# spdif_A.net
KiCad netlist of a schematic drawn in EAGLE
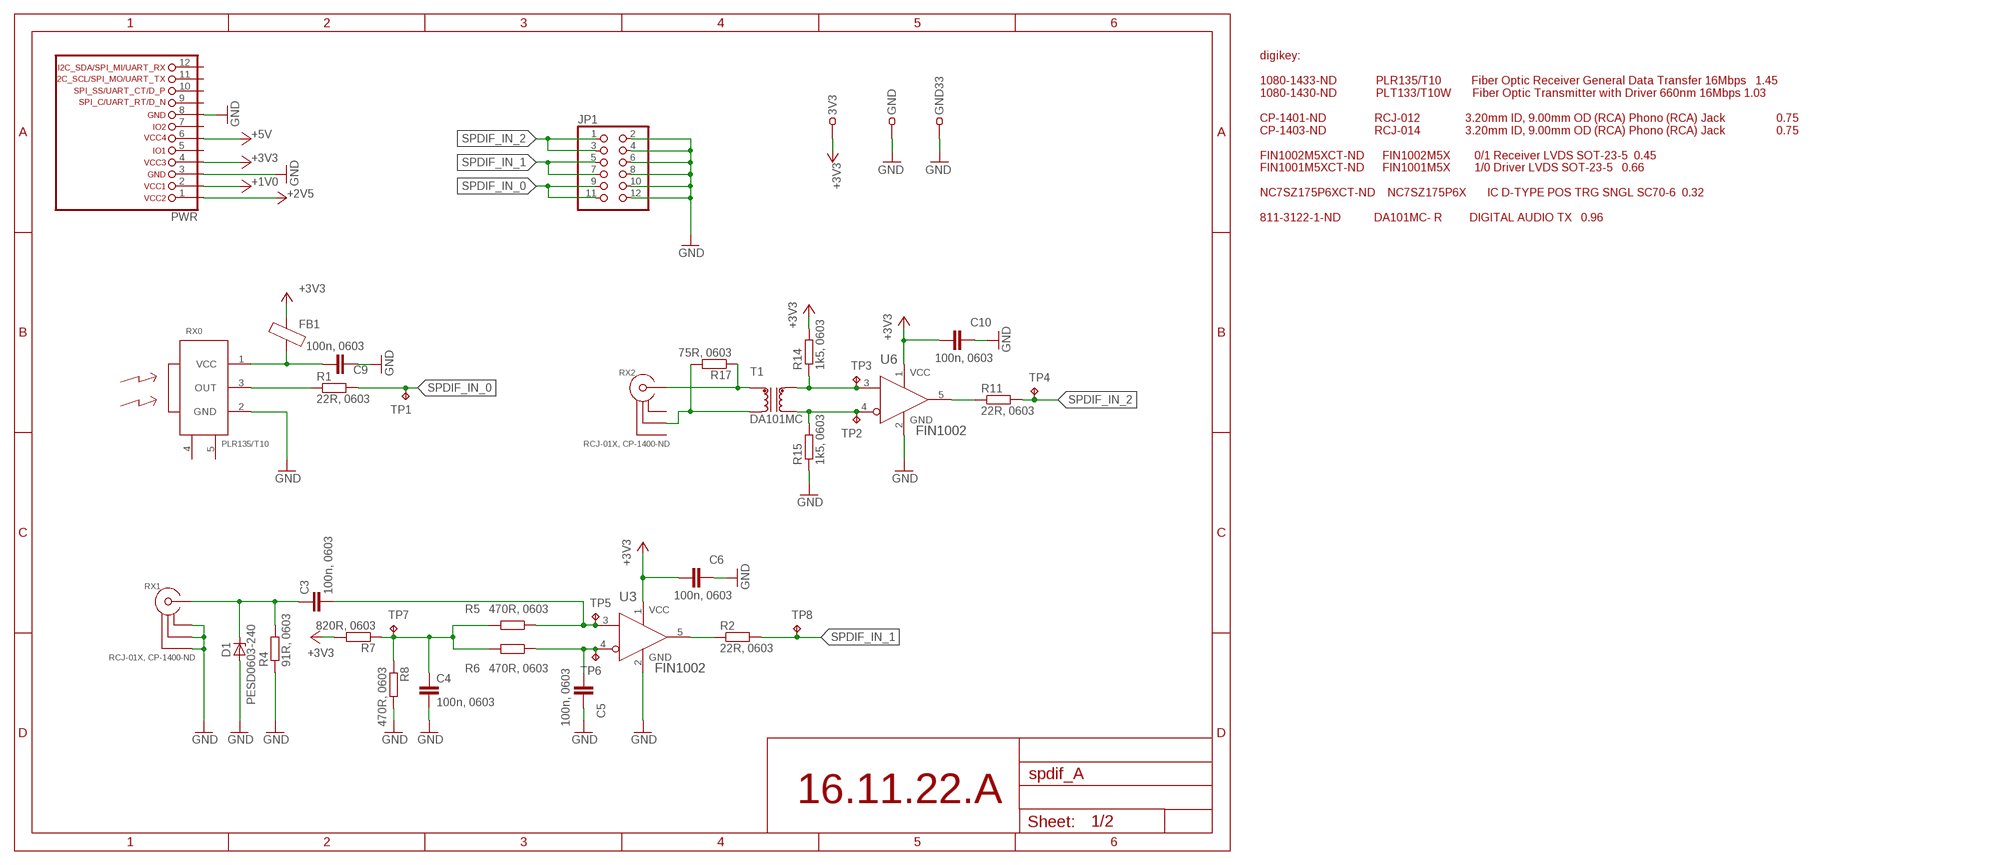
[diagram p0: schematic, sheet 1]
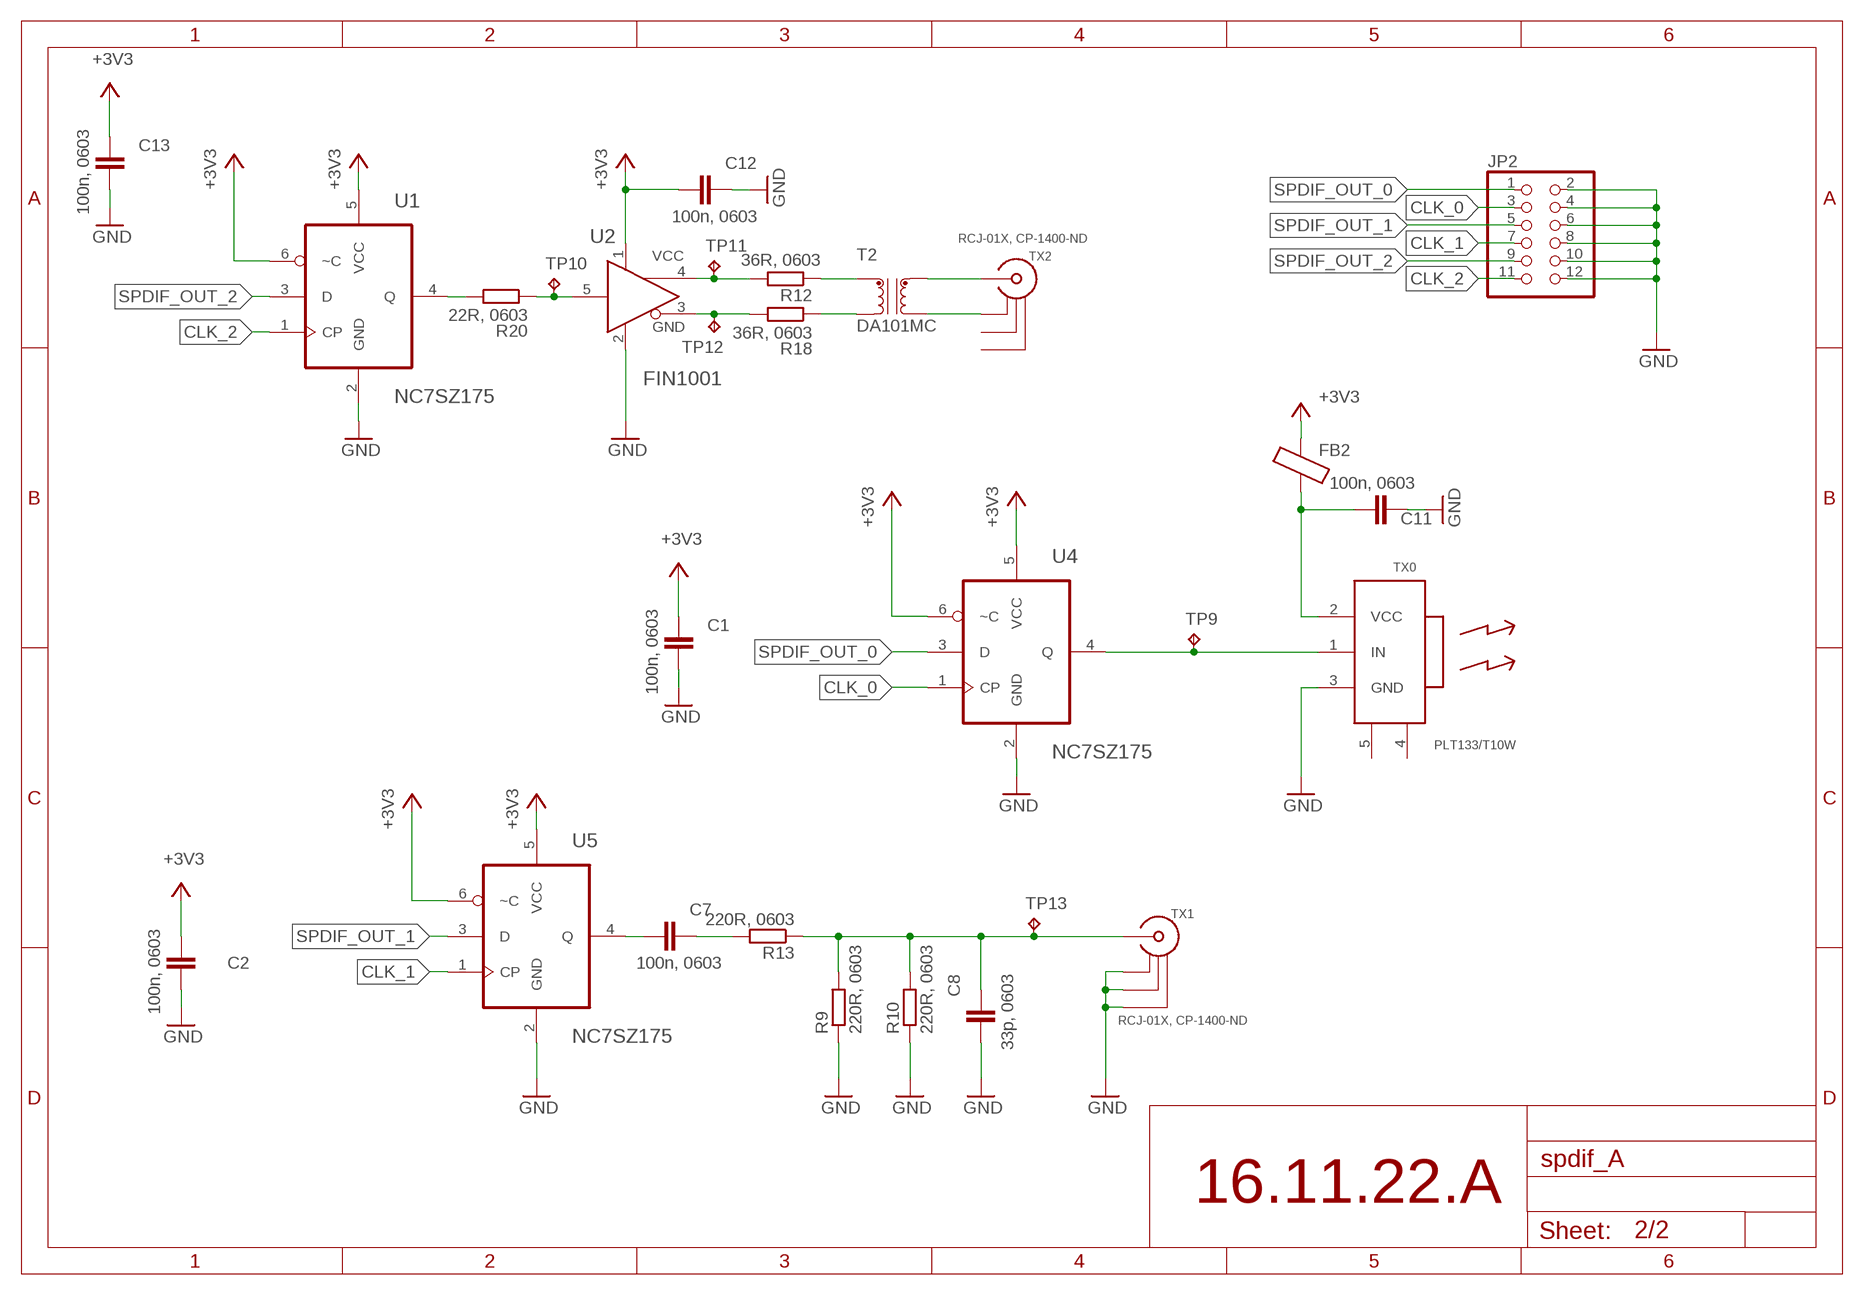
[diagram p1: schematic, sheet 2]

(export (version "E")
  (design (tool "Eeschema 10.0.6"))
  (components
    (comp (ref "3V3")
      (value "TEST-22-MULTICOMP")
      (footprint "eagle-import:TEST_1MM")
      (libsource (lib "eagle-import") (part "TEST-22-MULTICOMP"))
    )
    (comp (ref "C3")
      (value "100n, 0603")
      (footprint "eagle-import:C0603")
      (libsource (lib "eagle-import") (part "C-EUC0603"))
    )
    (comp (ref "C4")
      (value "100n, 0603")
      (footprint "eagle-import:C0603")
      (libsource (lib "eagle-import") (part "C-EUC0603"))
    )
    (comp (ref "C5")
      (value "100n, 0603")
      (footprint "eagle-import:C0603")
      (libsource (lib "eagle-import") (part "C-EUC0603"))
    )
    (comp (ref "C6")
      (value "100n, 0603")
      (footprint "eagle-import:C0603")
      (libsource (lib "eagle-import") (part "C-EUC0603"))
    )
    (comp (ref "C9")
      (value "100n, 0603")
      (footprint "eagle-import:C0603")
      (libsource (lib "eagle-import") (part "C-EUC0603"))
    )
    (comp (ref "C10")
      (value "100n, 0603")
      (footprint "eagle-import:C0603")
      (libsource (lib "eagle-import") (part "C-EUC0603"))
    )
    (comp (ref "D1")
      (value "PESD0603-240")
      (footprint "eagle-import:L0603")
      (libsource (lib "eagle-import") (part "ZDPESD0603-240"))
    )
    (comp (ref "FB1")
      (value "FB_0603")
      (footprint "eagle-import:L0603")
      (libsource (lib "eagle-import") (part "FB_0603"))
    )
    (comp (ref "GND")
      (value "TEST-22-MULTICOMP")
      (footprint "eagle-import:TEST_1MM")
      (libsource (lib "eagle-import") (part "TEST-22-MULTICOMP"))
    )
    (comp (ref "GND33")
      (value "TEST-22-MULTICOMP")
      (footprint "eagle-import:TEST_1MM")
      (libsource (lib "eagle-import") (part "TEST-22-MULTICOMP"))
    )
    (comp (ref "JP1")
      (value "PINHD-2X6/90")
      (footprint "eagle-import:2X06_90")
      (libsource (lib "eagle-import") (part "PINHD-2X6/90"))
    )
    (comp (ref "PWR")
      (value "LIWE_12_PIN_PWR7X7_COMPAT")
      (footprint "eagle-import:LIWE_12_PIN_7X7_COMPAT")
      (libsource (lib "eagle-import") (part "LIWE_12_PIN_PWR7X7_COMPAT"))
    )
    (comp (ref "R1")
      (value "22R, 0603")
      (footprint "eagle-import:R0603")
      (libsource (lib "eagle-import") (part "R-EU_R0603"))
    )
    (comp (ref "R2")
      (value "22R, 0603")
      (footprint "eagle-import:R0603")
      (libsource (lib "eagle-import") (part "R-EU_R0603"))
    )
    (comp (ref "R4")
      (value "91R, 0603")
      (footprint "eagle-import:R0603")
      (libsource (lib "eagle-import") (part "R-EU_R0603"))
    )
    (comp (ref "R5")
      (value "470R, 0603")
      (footprint "eagle-import:R0603")
      (libsource (lib "eagle-import") (part "R-EU_R0603"))
    )
    (comp (ref "R6")
      (value "470R, 0603")
      (footprint "eagle-import:R0603")
      (libsource (lib "eagle-import") (part "R-EU_R0603"))
    )
    (comp (ref "R7")
      (value "820R, 0603")
      (footprint "eagle-import:R0603")
      (libsource (lib "eagle-import") (part "R-EU_R0603"))
    )
    (comp (ref "R8")
      (value "470R, 0603")
      (footprint "eagle-import:R0603")
      (libsource (lib "eagle-import") (part "R-EU_R0603"))
    )
    (comp (ref "R11")
      (value "22R, 0603")
      (footprint "eagle-import:R0603")
      (libsource (lib "eagle-import") (part "R-EU_R0603"))
    )
    (comp (ref "R14")
      (value "1k5, 0603")
      (footprint "eagle-import:R0603")
      (libsource (lib "eagle-import") (part "R-EU_R0603"))
    )
    (comp (ref "R15")
      (value "1k5, 0603")
      (footprint "eagle-import:R0603")
      (libsource (lib "eagle-import") (part "R-EU_R0603"))
    )
    (comp (ref "R17")
      (value "75R, 0603")
      (footprint "eagle-import:R0603")
      (libsource (lib "eagle-import") (part "R-EU_R0603"))
    )
    (comp (ref "RX0")
      (value "PLR135/T10")
      (footprint "eagle-import:PLR135_T10")
      (libsource (lib "eagle-import") (part "PLR135_T10"))
    )
    (comp (ref "RX1")
      (value "RCJ-01X, CP-1400-ND")
      (footprint "eagle-import:RCJ-01X")
      (libsource (lib "eagle-import") (part "RCJ-01X"))
    )
    (comp (ref "RX2")
      (value "RCJ-01X, CP-1400-ND")
      (footprint "eagle-import:RCJ-01X")
      (libsource (lib "eagle-import") (part "RCJ-01X"))
    )
    (comp (ref "T1")
      (value "DA101MC")
      (footprint "eagle-import:DA101MC")
      (libsource (lib "eagle-import") (part "DA101MC"))
    )
    (comp (ref "TP1")
      (value "TPB1,27")
      (footprint "eagle-import:B1,27")
      (libsource (lib "eagle-import") (part "TPB1,27"))
    )
    (comp (ref "TP2")
      (value "TPB1,27")
      (footprint "eagle-import:B1,27")
      (libsource (lib "eagle-import") (part "TPB1,27"))
    )
    (comp (ref "TP3")
      (value "TPB1,27")
      (footprint "eagle-import:B1,27")
      (libsource (lib "eagle-import") (part "TPB1,27"))
    )
    (comp (ref "TP4")
      (value "TPB1,27")
      (footprint "eagle-import:B1,27")
      (libsource (lib "eagle-import") (part "TPB1,27"))
    )
    (comp (ref "TP5")
      (value "TPB1,27")
      (footprint "eagle-import:B1,27")
      (libsource (lib "eagle-import") (part "TPB1,27"))
    )
    (comp (ref "TP6")
      (value "TPB1,27")
      (footprint "eagle-import:B1,27")
      (libsource (lib "eagle-import") (part "TPB1,27"))
    )
    (comp (ref "TP7")
      (value "TPB1,27")
      (footprint "eagle-import:B1,27")
      (libsource (lib "eagle-import") (part "TPB1,27"))
    )
    (comp (ref "TP8")
      (value "TPB1,27")
      (footprint "eagle-import:B1,27")
      (libsource (lib "eagle-import") (part "TPB1,27"))
    )
    (comp (ref "U3")
      (value "FIN1002")
      (footprint "eagle-import:SOT95P280X140-5N")
      (libsource (lib "eagle-import") (part "FIN1002"))
    )
    (comp (ref "U6")
      (value "FIN1002")
      (footprint "eagle-import:SOT95P280X140-5N")
      (libsource (lib "eagle-import") (part "FIN1002"))
    )
    (comp (ref "C1")
      (value "100n, 0603")
      (footprint "eagle-import:C0603")
      (libsource (lib "eagle-import") (part "C-EUC0603"))
    )
    (comp (ref "C2")
      (value "100n, 0603")
      (footprint "eagle-import:C0603")
      (libsource (lib "eagle-import") (part "C-EUC0603"))
    )
    (comp (ref "C7")
      (value "100n, 0603")
      (footprint "eagle-import:C0603")
      (libsource (lib "eagle-import") (part "C-EUC0603"))
    )
    (comp (ref "C8")
      (value "33p, 0603")
      (footprint "eagle-import:C0603")
      (libsource (lib "eagle-import") (part "C-EUC0603"))
    )
    (comp (ref "C11")
      (value "100n, 0603")
      (footprint "eagle-import:C0603")
      (libsource (lib "eagle-import") (part "C-EUC0603"))
    )
    (comp (ref "C12")
      (value "100n, 0603")
      (footprint "eagle-import:C0603")
      (libsource (lib "eagle-import") (part "C-EUC0603"))
    )
    (comp (ref "C13")
      (value "100n, 0603")
      (footprint "eagle-import:C0603")
      (libsource (lib "eagle-import") (part "C-EUC0603"))
    )
    (comp (ref "FB2")
      (value "FB_0603")
      (footprint "eagle-import:L0603")
      (libsource (lib "eagle-import") (part "FB_0603"))
    )
    (comp (ref "JP2")
      (value "PINHD-2X6/90")
      (footprint "eagle-import:2X06_90")
      (libsource (lib "eagle-import") (part "PINHD-2X6/90"))
    )
    (comp (ref "R9")
      (value "220R, 0603")
      (footprint "eagle-import:R0603")
      (libsource (lib "eagle-import") (part "R-EU_R0603"))
    )
    (comp (ref "R10")
      (value "220R, 0603")
      (footprint "eagle-import:R0603")
      (libsource (lib "eagle-import") (part "R-EU_R0603"))
    )
    (comp (ref "R12")
      (value "36R, 0603")
      (footprint "eagle-import:R0603")
      (libsource (lib "eagle-import") (part "R-EU_R0603"))
    )
    (comp (ref "R13")
      (value "220R, 0603")
      (footprint "eagle-import:R0603")
      (libsource (lib "eagle-import") (part "R-EU_R0603"))
    )
    (comp (ref "R18")
      (value "36R, 0603")
      (footprint "eagle-import:R0603")
      (libsource (lib "eagle-import") (part "R-EU_R0603"))
    )
    (comp (ref "R20")
      (value "22R, 0603")
      (footprint "eagle-import:R0603")
      (libsource (lib "eagle-import") (part "R-EU_R0603"))
    )
    (comp (ref "T2")
      (value "DA101MC")
      (footprint "eagle-import:DA101MC")
      (libsource (lib "eagle-import") (part "DA101MC"))
    )
    (comp (ref "TP9")
      (value "TPB1,27")
      (footprint "eagle-import:B1,27")
      (libsource (lib "eagle-import") (part "TPB1,27"))
    )
    (comp (ref "TP10")
      (value "TPB1,27")
      (footprint "eagle-import:B1,27")
      (libsource (lib "eagle-import") (part "TPB1,27"))
    )
    (comp (ref "TP11")
      (value "TPB1,27")
      (footprint "eagle-import:B1,27")
      (libsource (lib "eagle-import") (part "TPB1,27"))
    )
    (comp (ref "TP12")
      (value "TPB1,27")
      (footprint "eagle-import:B1,27")
      (libsource (lib "eagle-import") (part "TPB1,27"))
    )
    (comp (ref "TP13")
      (value "TPB1,27")
      (footprint "eagle-import:B1,27")
      (libsource (lib "eagle-import") (part "TPB1,27"))
    )
    (comp (ref "TX0")
      (value "PLT133/T10W")
      (footprint "eagle-import:PLT133_T10W")
      (libsource (lib "eagle-import") (part "PLT133_T10W"))
    )
    (comp (ref "TX1")
      (value "RCJ-01X, CP-1400-ND")
      (footprint "eagle-import:RCJ-01X")
      (libsource (lib "eagle-import") (part "RCJ-01X"))
    )
    (comp (ref "TX2")
      (value "RCJ-01X, CP-1400-ND")
      (footprint "eagle-import:RCJ-01X")
      (libsource (lib "eagle-import") (part "RCJ-01X"))
    )
    (comp (ref "U1")
      (value "NC7SZ175")
      (footprint "eagle-import:SOT65P210X110-6N")
      (libsource (lib "eagle-import") (part "NC7SZ175"))
    )
    (comp (ref "U2")
      (value "FIN1001")
      (footprint "eagle-import:SOT95P280X140-5N")
      (libsource (lib "eagle-import") (part "FIN1001"))
    )
    (comp (ref "U4")
      (value "NC7SZ175")
      (footprint "eagle-import:SOT65P210X110-6N")
      (libsource (lib "eagle-import") (part "NC7SZ175"))
    )
    (comp (ref "U5")
      (value "NC7SZ175")
      (footprint "eagle-import:SOT65P210X110-6N")
      (libsource (lib "eagle-import") (part "NC7SZ175"))
    )
  )
  (nets
    (net (code "1") (name "+1V0") (class "Default")
      (node (ref "PWR") (pin "2") (pinfunction "2_2") (pintype "passive"))
    )
    (net (code "2") (name "+2V5") (class "Default")
      (node (ref "PWR") (pin "1") (pinfunction "1_1") (pintype "passive"))
    )
    (net (code "3") (name "+3V3") (class "Default")
      (node (ref "3V3") (pin "1") (pinfunction "1_1") (pintype "passive"))
      (node (ref "C1") (pin "2") (pinfunction "2_2") (pintype "passive"))
      (node (ref "C10") (pin "2") (pinfunction "2_2") (pintype "passive"))
      (node (ref "C12") (pin "2") (pinfunction "2_2") (pintype "passive"))
      (node (ref "C13") (pin "2") (pinfunction "2_2") (pintype "passive"))
      (node (ref "C2") (pin "2") (pinfunction "2_2") (pintype "passive"))
      (node (ref "C6") (pin "2") (pinfunction "2_2") (pintype "passive"))
      (node (ref "FB1") (pin "2") (pinfunction "P$2_2") (pintype "bidirectional"))
      (node (ref "FB2") (pin "2") (pinfunction "P$2_2") (pintype "bidirectional"))
      (node (ref "PWR") (pin "4") (pinfunction "4_4") (pintype "passive"))
      (node (ref "R14") (pin "2") (pinfunction "2_2") (pintype "passive"))
      (node (ref "R7") (pin "2") (pinfunction "2_2") (pintype "passive"))
      (node (ref "U1") (pin "5") (pinfunction "VCC_5") (pintype "power_in"))
      (node (ref "U1") (pin "6") (pinfunction "~{C}_6") (pintype "input"))
      (node (ref "U2") (pin "1") (pinfunction "VCC_1") (pintype "power_in"))
      (node (ref "U3") (pin "1") (pinfunction "VCC_1") (pintype "power_in"))
      (node (ref "U4") (pin "5") (pinfunction "VCC_5") (pintype "power_in"))
      (node (ref "U4") (pin "6") (pinfunction "~{C}_6") (pintype "input"))
      (node (ref "U5") (pin "5") (pinfunction "VCC_5") (pintype "power_in"))
      (node (ref "U5") (pin "6") (pinfunction "~{C}_6") (pintype "input"))
      (node (ref "U6") (pin "1") (pinfunction "VCC_1") (pintype "power_in"))
    )
    (net (code "4") (name "+5V") (class "Default")
      (node (ref "PWR") (pin "6") (pinfunction "6_6") (pintype "passive"))
    )
    (net (code "5") (name "CLK_0") (class "Default")
      (node (ref "JP2") (pin "3") (pinfunction "3_3") (pintype "passive"))
      (node (ref "U4") (pin "1") (pinfunction "CP_1") (pintype "input"))
    )
    (net (code "6") (name "CLK_1") (class "Default")
      (node (ref "JP2") (pin "7") (pinfunction "7_7") (pintype "passive"))
      (node (ref "U5") (pin "1") (pinfunction "CP_1") (pintype "input"))
    )
    (net (code "7") (name "CLK_2") (class "Default")
      (node (ref "JP2") (pin "11") (pinfunction "11_11") (pintype "passive"))
      (node (ref "U1") (pin "1") (pinfunction "CP_1") (pintype "input"))
    )
    (net (code "8") (name "GND") (class "Default")
      (node (ref "C1") (pin "1") (pinfunction "1_1") (pintype "passive"))
      (node (ref "C10") (pin "1") (pinfunction "1_1") (pintype "passive"))
      (node (ref "C11") (pin "1") (pinfunction "1_1") (pintype "passive"))
      (node (ref "C12") (pin "1") (pinfunction "1_1") (pintype "passive"))
      (node (ref "C13") (pin "1") (pinfunction "1_1") (pintype "passive"))
      (node (ref "C2") (pin "1") (pinfunction "1_1") (pintype "passive"))
      (node (ref "C4") (pin "2") (pinfunction "2_2") (pintype "passive"))
      (node (ref "C5") (pin "1") (pinfunction "1_1") (pintype "passive"))
      (node (ref "C6") (pin "1") (pinfunction "1_1") (pintype "passive"))
      (node (ref "C8") (pin "2") (pinfunction "2_2") (pintype "passive"))
      (node (ref "C9") (pin "1") (pinfunction "1_1") (pintype "passive"))
      (node (ref "D1") (pin "1") (pinfunction "A_1") (pintype "passive"))
      (node (ref "GND") (pin "1") (pinfunction "1_1") (pintype "passive"))
      (node (ref "GND33") (pin "1") (pinfunction "1_1") (pintype "passive"))
      (node (ref "JP1") (pin "10") (pinfunction "10_10") (pintype "passive"))
      (node (ref "JP1") (pin "12") (pinfunction "12_12") (pintype "passive"))
      (node (ref "JP1") (pin "2") (pinfunction "2_2") (pintype "passive"))
      (node (ref "JP1") (pin "4") (pinfunction "4_4") (pintype "passive"))
      (node (ref "JP1") (pin "6") (pinfunction "6_6") (pintype "passive"))
      (node (ref "JP1") (pin "8") (pinfunction "8_8") (pintype "passive"))
      (node (ref "JP2") (pin "10") (pinfunction "10_10") (pintype "passive"))
      (node (ref "JP2") (pin "12") (pinfunction "12_12") (pintype "passive"))
      (node (ref "JP2") (pin "2") (pinfunction "2_2") (pintype "passive"))
      (node (ref "JP2") (pin "4") (pinfunction "4_4") (pintype "passive"))
      (node (ref "JP2") (pin "6") (pinfunction "6_6") (pintype "passive"))
      (node (ref "JP2") (pin "8") (pinfunction "8_8") (pintype "passive"))
      (node (ref "PWR") (pin "3") (pinfunction "3_3") (pintype "passive"))
      (node (ref "PWR") (pin "8") (pinfunction "8_8") (pintype "passive"))
      (node (ref "R10") (pin "1") (pinfunction "1_1") (pintype "passive"))
      (node (ref "R15") (pin "1") (pinfunction "1_1") (pintype "passive"))
      (node (ref "R4") (pin "1") (pinfunction "1_1") (pintype "passive"))
      (node (ref "R8") (pin "2") (pinfunction "2_2") (pintype "passive"))
      (node (ref "R9") (pin "1") (pinfunction "1_1") (pintype "passive"))
      (node (ref "RX0") (pin "2") (pinfunction "GND_2") (pintype "output"))
      (node (ref "RX1") (pin "20") (pinfunction "GND1_20") (pintype "output"))
      (node (ref "RX1") (pin "21") (pinfunction "GND2_21") (pintype "output"))
      (node (ref "RX1") (pin "22") (pinfunction "GND3_22") (pintype "output"))
      (node (ref "TX0") (pin "3") (pinfunction "GND_3") (pintype "output"))
      (node (ref "TX1") (pin "20") (pinfunction "GND1_20") (pintype "output"))
      (node (ref "TX1") (pin "21") (pinfunction "GND2_21") (pintype "output"))
      (node (ref "TX1") (pin "22") (pinfunction "GND3_22") (pintype "output"))
      (node (ref "U1") (pin "2") (pinfunction "GND_2") (pintype "passive"))
      (node (ref "U2") (pin "2") (pinfunction "GND_2") (pintype "passive"))
      (node (ref "U3") (pin "2") (pinfunction "GND_2") (pintype "passive"))
      (node (ref "U4") (pin "2") (pinfunction "GND_2") (pintype "passive"))
      (node (ref "U5") (pin "2") (pinfunction "GND_2") (pintype "passive"))
      (node (ref "U6") (pin "2") (pinfunction "GND_2") (pintype "passive"))
    )
    (net (code "9") (name "Net-(C4-Pad1)") (class "Default")
      (node (ref "C4") (pin "1") (pinfunction "1_1") (pintype "passive"))
      (node (ref "R5") (pin "2") (pinfunction "2_2") (pintype "passive"))
      (node (ref "R6") (pin "2") (pinfunction "2_2") (pintype "passive"))
      (node (ref "R7") (pin "1") (pinfunction "1_1") (pintype "passive"))
      (node (ref "R8") (pin "1") (pinfunction "1_1") (pintype "passive"))
      (node (ref "TP7") (pin "TP") (pinfunction "TP_TP") (pintype "input"))
    )
    (net (code "10") (name "Net-(C7-Pad1)") (class "Default")
      (node (ref "C7") (pin "1") (pinfunction "1_1") (pintype "passive"))
      (node (ref "R13") (pin "2") (pinfunction "2_2") (pintype "passive"))
    )
    (net (code "11") (name "Net-(D1-C)") (class "Default")
      (node (ref "C3") (pin "1") (pinfunction "1_1") (pintype "passive"))
      (node (ref "D1") (pin "2") (pinfunction "C_2") (pintype "passive"))
      (node (ref "R4") (pin "2") (pinfunction "2_2") (pintype "passive"))
      (node (ref "RX1") (pin "1") (pinfunction "SIG_1") (pintype "output"))
    )
    (net (code "12") (name "Net-(FB1-P$1)") (class "Default")
      (node (ref "C9") (pin "2") (pinfunction "2_2") (pintype "passive"))
      (node (ref "FB1") (pin "1") (pinfunction "P$1_1") (pintype "bidirectional"))
      (node (ref "RX0") (pin "1") (pinfunction "VCC_1") (pintype "output"))
    )
    (net (code "13") (name "Net-(FB2-P$1)") (class "Default")
      (node (ref "C11") (pin "2") (pinfunction "2_2") (pintype "passive"))
      (node (ref "FB2") (pin "1") (pinfunction "P$1_1") (pintype "bidirectional"))
      (node (ref "TX0") (pin "2") (pinfunction "VCC_2") (pintype "output"))
    )
    (net (code "14") (name "Net-(R12-Pad1)") (class "Default")
      (node (ref "R12") (pin "1") (pinfunction "1_1") (pintype "passive"))
      (node (ref "T2") (pin "1") (pinfunction "1_1") (pintype "bidirectional"))
    )
    (net (code "15") (name "Net-(R18-Pad1)") (class "Default")
      (node (ref "R18") (pin "1") (pinfunction "1_1") (pintype "passive"))
      (node (ref "T2") (pin "3") (pinfunction "3_3") (pintype "bidirectional"))
    )
    (net (code "16") (name "Net-(RX0-OUT)") (class "Default")
      (node (ref "R1") (pin "1") (pinfunction "1_1") (pintype "passive"))
      (node (ref "RX0") (pin "3") (pinfunction "OUT_3") (pintype "output"))
    )
    (net (code "17") (name "Net-(RX2-GND2)") (class "Default")
      (node (ref "R17") (pin "2") (pinfunction "2_2") (pintype "passive"))
      (node (ref "RX2") (pin "21") (pinfunction "GND2_21") (pintype "output"))
      (node (ref "T1") (pin "3") (pinfunction "3_3") (pintype "bidirectional"))
    )
    (net (code "18") (name "Net-(RX2-SIG)") (class "Default")
      (node (ref "R17") (pin "1") (pinfunction "1_1") (pintype "passive"))
      (node (ref "RX2") (pin "1") (pinfunction "SIG_1") (pintype "output"))
      (node (ref "T1") (pin "1") (pinfunction "1_1") (pintype "bidirectional"))
    )
    (net (code "19") (name "Net-(TX0-IN)") (class "Default")
      (node (ref "TP9") (pin "TP") (pinfunction "TP_TP") (pintype "input"))
      (node (ref "TX0") (pin "1") (pinfunction "IN_1") (pintype "output"))
      (node (ref "U4") (pin "4") (pinfunction "Q_4") (pintype "output"))
    )
    (net (code "20") (name "Net-(TX1-SIG)") (class "Default")
      (node (ref "C8") (pin "1") (pinfunction "1_1") (pintype "passive"))
      (node (ref "R10") (pin "2") (pinfunction "2_2") (pintype "passive"))
      (node (ref "R13") (pin "1") (pinfunction "1_1") (pintype "passive"))
      (node (ref "R9") (pin "2") (pinfunction "2_2") (pintype "passive"))
      (node (ref "TP13") (pin "TP") (pinfunction "TP_TP") (pintype "input"))
      (node (ref "TX1") (pin "1") (pinfunction "SIG_1") (pintype "output"))
    )
    (net (code "21") (name "Net-(TX2-GND1)") (class "Default")
      (node (ref "T2") (pin "4") (pinfunction "4_4") (pintype "bidirectional"))
      (node (ref "TX2") (pin "20") (pinfunction "GND1_20") (pintype "output"))
    )
    (net (code "22") (name "Net-(TX2-SIG)") (class "Default")
      (node (ref "T2") (pin "6") (pinfunction "6_6") (pintype "bidirectional"))
      (node (ref "TX2") (pin "1") (pinfunction "SIG_1") (pintype "output"))
    )
    (net (code "23") (name "Net-(U1-Q)") (class "Default")
      (node (ref "R20") (pin "2") (pinfunction "2_2") (pintype "passive"))
      (node (ref "U1") (pin "4") (pinfunction "Q_4") (pintype "output"))
    )
    (net (code "24") (name "Net-(U2-RIN)") (class "Default")
      (node (ref "R20") (pin "1") (pinfunction "1_1") (pintype "passive"))
      (node (ref "TP10") (pin "TP") (pinfunction "TP_TP") (pintype "input"))
      (node (ref "U2") (pin "5") (pinfunction "RIN_5") (pintype "input"))
    )
    (net (code "25") (name "Net-(U2-ROUT+)") (class "Default")
      (node (ref "R12") (pin "2") (pinfunction "2_2") (pintype "passive"))
      (node (ref "TP11") (pin "TP") (pinfunction "TP_TP") (pintype "input"))
      (node (ref "U2") (pin "4") (pinfunction "ROUT+_4") (pintype "output"))
    )
    (net (code "26") (name "Net-(U2-ROUT-)") (class "Default")
      (node (ref "R18") (pin "2") (pinfunction "2_2") (pintype "passive"))
      (node (ref "TP12") (pin "TP") (pinfunction "TP_TP") (pintype "input"))
      (node (ref "U2") (pin "3") (pinfunction "ROUT-_3") (pintype "output"))
    )
    (net (code "27") (name "Net-(U3-RIN+)") (class "Default")
      (node (ref "C3") (pin "2") (pinfunction "2_2") (pintype "passive"))
      (node (ref "R5") (pin "1") (pinfunction "1_1") (pintype "passive"))
      (node (ref "TP5") (pin "TP") (pinfunction "TP_TP") (pintype "input"))
      (node (ref "U3") (pin "3") (pinfunction "RIN+_3") (pintype "input"))
    )
    (net (code "28") (name "Net-(U3-RIN-)") (class "Default")
      (node (ref "C5") (pin "2") (pinfunction "2_2") (pintype "passive"))
      (node (ref "R6") (pin "1") (pinfunction "1_1") (pintype "passive"))
      (node (ref "TP6") (pin "TP") (pinfunction "TP_TP") (pintype "input"))
      (node (ref "U3") (pin "4") (pinfunction "RIN-_4") (pintype "input"))
    )
    (net (code "29") (name "Net-(U3-ROUT)") (class "Default")
      (node (ref "R2") (pin "1") (pinfunction "1_1") (pintype "passive"))
      (node (ref "U3") (pin "5") (pinfunction "ROUT_5") (pintype "output"))
    )
    (net (code "30") (name "Net-(U5-Q)") (class "Default")
      (node (ref "C7") (pin "2") (pinfunction "2_2") (pintype "passive"))
      (node (ref "U5") (pin "4") (pinfunction "Q_4") (pintype "output"))
    )
    (net (code "31") (name "Net-(U6-RIN+)") (class "Default")
      (node (ref "R14") (pin "1") (pinfunction "1_1") (pintype "passive"))
      (node (ref "T1") (pin "6") (pinfunction "6_6") (pintype "bidirectional"))
      (node (ref "TP3") (pin "TP") (pinfunction "TP_TP") (pintype "input"))
      (node (ref "U6") (pin "3") (pinfunction "RIN+_3") (pintype "input"))
    )
    (net (code "32") (name "Net-(U6-RIN-)") (class "Default")
      (node (ref "R15") (pin "2") (pinfunction "2_2") (pintype "passive"))
      (node (ref "T1") (pin "4") (pinfunction "4_4") (pintype "bidirectional"))
      (node (ref "TP2") (pin "TP") (pinfunction "TP_TP") (pintype "input"))
      (node (ref "U6") (pin "4") (pinfunction "RIN-_4") (pintype "input"))
    )
    (net (code "33") (name "Net-(U6-ROUT)") (class "Default")
      (node (ref "R11") (pin "1") (pinfunction "1_1") (pintype "passive"))
      (node (ref "U6") (pin "5") (pinfunction "ROUT_5") (pintype "output"))
    )
    (net (code "34") (name "SPDIF_IN_0") (class "Default")
      (node (ref "JP1") (pin "11") (pinfunction "11_11") (pintype "passive"))
      (node (ref "JP1") (pin "9") (pinfunction "9_9") (pintype "passive"))
      (node (ref "R1") (pin "2") (pinfunction "2_2") (pintype "passive"))
      (node (ref "TP1") (pin "TP") (pinfunction "TP_TP") (pintype "input"))
    )
    (net (code "35") (name "SPDIF_IN_1") (class "Default")
      (node (ref "JP1") (pin "5") (pinfunction "5_5") (pintype "passive"))
      (node (ref "JP1") (pin "7") (pinfunction "7_7") (pintype "passive"))
      (node (ref "R2") (pin "2") (pinfunction "2_2") (pintype "passive"))
      (node (ref "TP8") (pin "TP") (pinfunction "TP_TP") (pintype "input"))
    )
    (net (code "36") (name "SPDIF_IN_2") (class "Default")
      (node (ref "JP1") (pin "1") (pinfunction "1_1") (pintype "passive"))
      (node (ref "JP1") (pin "3") (pinfunction "3_3") (pintype "passive"))
      (node (ref "R11") (pin "2") (pinfunction "2_2") (pintype "passive"))
      (node (ref "TP4") (pin "TP") (pinfunction "TP_TP") (pintype "input"))
    )
    (net (code "37") (name "SPDIF_OUT_0") (class "Default")
      (node (ref "JP2") (pin "1") (pinfunction "1_1") (pintype "passive"))
      (node (ref "U4") (pin "3") (pinfunction "D_3") (pintype "input"))
    )
    (net (code "38") (name "SPDIF_OUT_1") (class "Default")
      (node (ref "JP2") (pin "5") (pinfunction "5_5") (pintype "passive"))
      (node (ref "U5") (pin "3") (pinfunction "D_3") (pintype "input"))
    )
    (net (code "39") (name "SPDIF_OUT_2") (class "Default")
      (node (ref "JP2") (pin "9") (pinfunction "9_9") (pintype "passive"))
      (node (ref "U1") (pin "3") (pinfunction "D_3") (pintype "input"))
    )
    (net (code "40") (name "unconnected-(PWR-Pad5)") (class "Default")
      (node (ref "PWR") (pin "5") (pinfunction "5_5") (pintype "passive"))
    )
    (net (code "41") (name "unconnected-(PWR-Pad7)") (class "Default")
      (node (ref "PWR") (pin "7") (pinfunction "7_7") (pintype "passive"))
    )
    (net (code "42") (name "unconnected-(PWR-Pad9)") (class "Default")
      (node (ref "PWR") (pin "9") (pinfunction "9_9") (pintype "passive"))
    )
    (net (code "43") (name "unconnected-(PWR-Pad10)") (class "Default")
      (node (ref "PWR") (pin "10") (pinfunction "10_10") (pintype "passive"))
    )
    (net (code "44") (name "unconnected-(PWR-Pad11)") (class "Default")
      (node (ref "PWR") (pin "11") (pinfunction "11_11") (pintype "passive"))
    )
    (net (code "45") (name "unconnected-(PWR-Pad12)") (class "Default")
      (node (ref "PWR") (pin "12") (pinfunction "12_12") (pintype "passive"))
    )
    (net (code "46") (name "unconnected-(RX0-NC0-Pad4)") (class "Default")
      (node (ref "RX0") (pin "4") (pinfunction "NC0_4") (pintype "output"))
    )
    (net (code "47") (name "unconnected-(RX0-NC1-Pad5)") (class "Default")
      (node (ref "RX0") (pin "5") (pinfunction "NC1_5") (pintype "output"))
    )
    (net (code "48") (name "unconnected-(RX2-GND1-Pad20)") (class "Default")
      (node (ref "RX2") (pin "20") (pinfunction "GND1_20") (pintype "output"))
    )
    (net (code "49") (name "unconnected-(RX2-GND3-Pad22)") (class "Default")
      (node (ref "RX2") (pin "22") (pinfunction "GND3_22") (pintype "output"))
    )
    (net (code "50") (name "unconnected-(TX0-NC0-Pad4)") (class "Default")
      (node (ref "TX0") (pin "4") (pinfunction "NC0_4") (pintype "output"))
    )
    (net (code "51") (name "unconnected-(TX0-NC1-Pad5)") (class "Default")
      (node (ref "TX0") (pin "5") (pinfunction "NC1_5") (pintype "output"))
    )
    (net (code "52") (name "unconnected-(TX2-GND2-Pad21)") (class "Default")
      (node (ref "TX2") (pin "21") (pinfunction "GND2_21") (pintype "output"))
    )
    (net (code "53") (name "unconnected-(TX2-GND3-Pad22)") (class "Default")
      (node (ref "TX2") (pin "22") (pinfunction "GND3_22") (pintype "output"))
    )
  )
)
